# io8.net
KiCad netlist of a schematic drawn in EAGLE
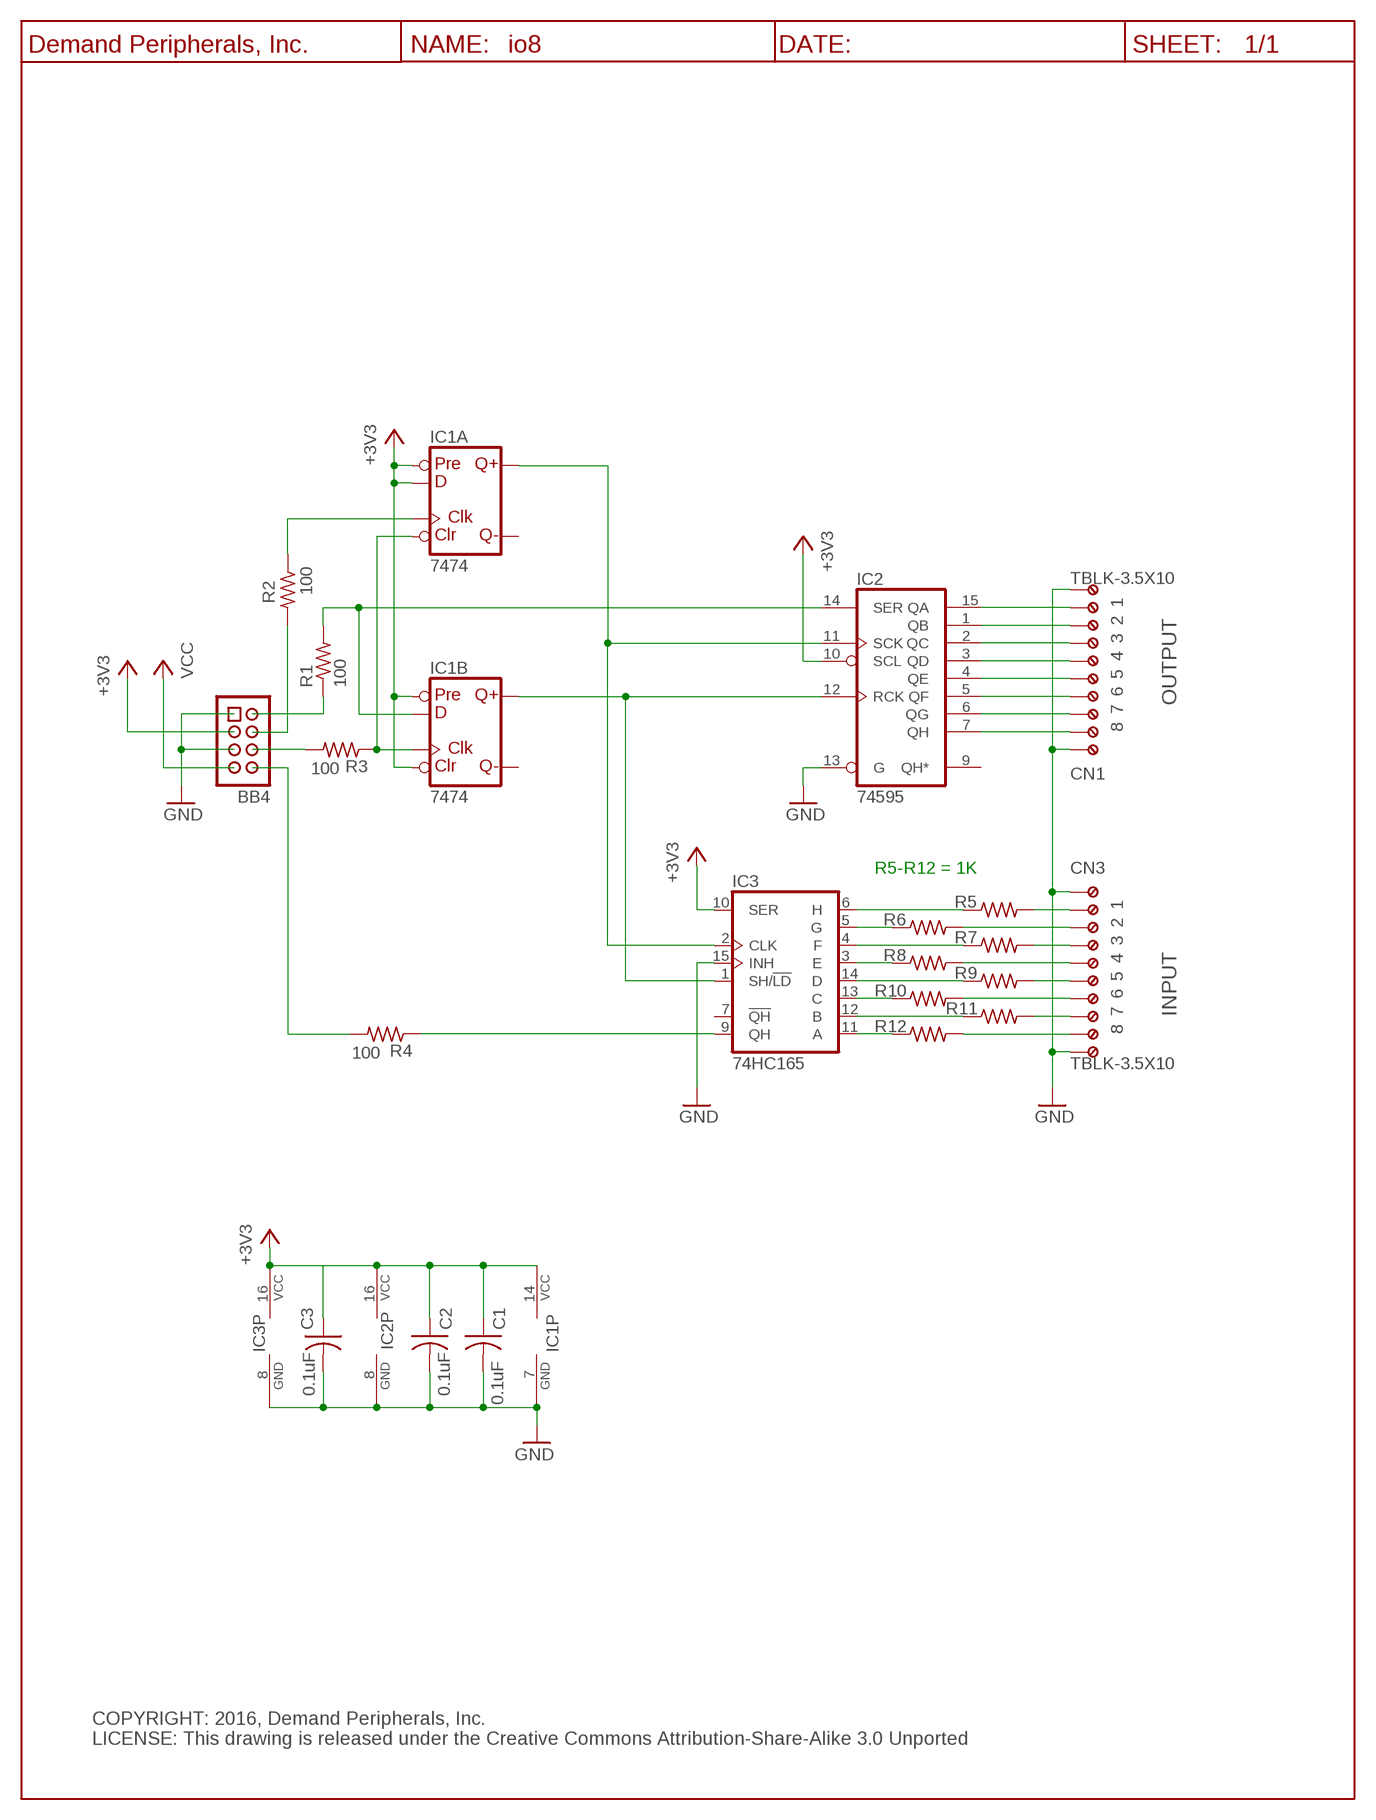
[diagram p0: schematic, sheet 1]

(export (version "E")
  (design (tool "Eeschema 10.0.6"))
  (components
    (comp (ref "BB4")
      (value "Hdr_4x2")
      (footprint "eagle-import:HDR-4X2")
      (libsource (lib "eagle-import") (part "HDR-4X2-SHR"))
    )
    (comp (ref "C1")
      (value "0.1uF")
      (footprint "eagle-import:C0603")
      (libsource (lib "eagle-import") (part "C0.1UF_C0603"))
    )
    (comp (ref "C2")
      (value "0.1uF")
      (footprint "eagle-import:C0603")
      (libsource (lib "eagle-import") (part "C0.1UF_C0603"))
    )
    (comp (ref "C3")
      (value "0.1uF")
      (footprint "eagle-import:C0603")
      (libsource (lib "eagle-import") (part "C0.1UF_C0603"))
    )
    (comp (ref "CN1")
      (value "TBLK-3.5X10")
      (footprint "eagle-import:TBLK-3.5X10")
      (libsource (lib "eagle-import") (part "TBLK-3.5X10"))
    )
    (comp (ref "CN3")
      (value "TBLK-3.5X10")
      (footprint "eagle-import:TBLK-3.5X10")
      (libsource (lib "eagle-import") (part "TBLK-3.5X10"))
    )
    (comp (ref "IC1")
      (value "7474")
      (footprint "eagle-import:SO14")
      (libsource (lib "eagle-import") (part "74AHC74"))
    )
    (comp (ref "IC2")
      (value "74595")
      (footprint "eagle-import:SO16")
      (libsource (lib "eagle-import") (part "74595"))
    )
    (comp (ref "IC3")
      (value "74HC165")
      (footprint "eagle-import:SO16")
      (libsource (lib "eagle-import") (part "74HC165"))
    )
    (comp (ref "R1")
      (value "100")
      (footprint "eagle-import:R0603")
      (libsource (lib "eagle-import") (part "R100_R0603"))
    )
    (comp (ref "R2")
      (value "100")
      (footprint "eagle-import:R0603")
      (libsource (lib "eagle-import") (part "R100_R0603"))
    )
    (comp (ref "R3")
      (value "100")
      (footprint "eagle-import:R0603")
      (libsource (lib "eagle-import") (part "R100_R0603"))
    )
    (comp (ref "R4")
      (value "100")
      (footprint "eagle-import:R0603")
      (libsource (lib "eagle-import") (part "R100_R0603"))
    )
    (comp (ref "R5")
      (value "R1K_R0603")
      (footprint "eagle-import:R0603")
      (libsource (lib "eagle-import") (part "R1K_R0603"))
    )
    (comp (ref "R6")
      (value "R1K_R0603")
      (footprint "eagle-import:R0603")
      (libsource (lib "eagle-import") (part "R1K_R0603"))
    )
    (comp (ref "R7")
      (value "R1K_R0603")
      (footprint "eagle-import:R0603")
      (libsource (lib "eagle-import") (part "R1K_R0603"))
    )
    (comp (ref "R8")
      (value "R1K_R0603")
      (footprint "eagle-import:R0603")
      (libsource (lib "eagle-import") (part "R1K_R0603"))
    )
    (comp (ref "R9")
      (value "R1K_R0603")
      (footprint "eagle-import:R0603")
      (libsource (lib "eagle-import") (part "R1K_R0603"))
    )
    (comp (ref "R10")
      (value "R1K_R0603")
      (footprint "eagle-import:R0603")
      (libsource (lib "eagle-import") (part "R1K_R0603"))
    )
    (comp (ref "R11")
      (value "R1K_R0603")
      (footprint "eagle-import:R0603")
      (libsource (lib "eagle-import") (part "R1K_R0603"))
    )
    (comp (ref "R12")
      (value "R1K_R0603")
      (footprint "eagle-import:R0603")
      (libsource (lib "eagle-import") (part "R1K_R0603"))
    )
    (comp (ref "U$5")
      (value "DP_FRAME_P")
      (footprint "eagle-import:P_FRAME")
      (libsource (lib "eagle-import") (part "DP_FRAME_P"))
    )
  )
  (nets
    (net (code "1") (name "+3V3") (class "Default")
      (node (ref "BB4") (pin "3") (pinfunction "3_3") (pintype "passive"))
      (node (ref "C1") (pin "1") (pinfunction "1_1") (pintype "passive"))
      (node (ref "C2") (pin "1") (pinfunction "1_1") (pintype "passive"))
      (node (ref "C3") (pin "1") (pinfunction "1_1") (pintype "passive"))
      (node (ref "IC1") (pin "10") (pinfunction "PRE_10") (pintype "input"))
      (node (ref "IC1") (pin "13") (pinfunction "CLR_13") (pintype "input"))
      (node (ref "IC1") (pin "14") (pinfunction "VCC_14") (pintype "power_in"))
      (node (ref "IC1") (pin "2") (pinfunction "D_2") (pintype "input"))
      (node (ref "IC1") (pin "4") (pinfunction "PRE_4") (pintype "input"))
      (node (ref "IC2") (pin "10") (pinfunction "SCL_10") (pintype "input"))
      (node (ref "IC2") (pin "16") (pinfunction "VCC_16") (pintype "power_in"))
      (node (ref "IC3") (pin "10") (pinfunction "SER_10") (pintype "input"))
      (node (ref "IC3") (pin "16") (pinfunction "VCC_16") (pintype "power_in"))
    )
    (net (code "2") (name "GND") (class "Default")
      (node (ref "BB4") (pin "1") (pinfunction "1_1") (pintype "passive"))
      (node (ref "BB4") (pin "5") (pinfunction "5_5") (pintype "passive"))
      (node (ref "C1") (pin "2") (pinfunction "2_2") (pintype "passive"))
      (node (ref "C2") (pin "2") (pinfunction "2_2") (pintype "passive"))
      (node (ref "C3") (pin "2") (pinfunction "2_2") (pintype "passive"))
      (node (ref "CN1") (pin "1") (pinfunction "KL_1") (pintype "passive"))
      (node (ref "CN1") (pin "10") (pinfunction "KL9_10") (pintype "passive"))
      (node (ref "CN3") (pin "1") (pinfunction "KL_1") (pintype "passive"))
      (node (ref "CN3") (pin "10") (pinfunction "KL9_10") (pintype "passive"))
      (node (ref "IC1") (pin "7") (pinfunction "GND_7") (pintype "power_in"))
      (node (ref "IC2") (pin "13") (pinfunction "G_13") (pintype "input"))
      (node (ref "IC2") (pin "8") (pinfunction "GND_8") (pintype "power_in"))
      (node (ref "IC3") (pin "15") (pinfunction "INH_15") (pintype "input"))
      (node (ref "IC3") (pin "8") (pinfunction "GND_8") (pintype "power_in"))
    )
    (net (code "3") (name "Net-(BB4-Pad2)") (class "Default")
      (node (ref "BB4") (pin "2") (pinfunction "2_2") (pintype "passive"))
      (node (ref "R1") (pin "1") (pinfunction "1_1") (pintype "passive"))
    )
    (net (code "4") (name "Net-(BB4-Pad4)") (class "Default")
      (node (ref "BB4") (pin "4") (pinfunction "4_4") (pintype "passive"))
      (node (ref "R2") (pin "2") (pinfunction "2_2") (pintype "passive"))
    )
    (net (code "5") (name "Net-(BB4-Pad6)") (class "Default")
      (node (ref "BB4") (pin "6") (pinfunction "6_6") (pintype "passive"))
      (node (ref "R3") (pin "2") (pinfunction "2_2") (pintype "passive"))
    )
    (net (code "6") (name "Net-(BB4-Pad8)") (class "Default")
      (node (ref "BB4") (pin "8") (pinfunction "8_8") (pintype "passive"))
      (node (ref "R4") (pin "2") (pinfunction "2_2") (pintype "passive"))
    )
    (net (code "7") (name "Net-(CN1-KL1)") (class "Default")
      (node (ref "CN1") (pin "2") (pinfunction "KL1_2") (pintype "passive"))
      (node (ref "IC2") (pin "7") (pinfunction "QH_7") (pintype "tri_state"))
    )
    (net (code "8") (name "Net-(CN1-KL2)") (class "Default")
      (node (ref "CN1") (pin "3") (pinfunction "KL2_3") (pintype "passive"))
      (node (ref "IC2") (pin "6") (pinfunction "QG_6") (pintype "tri_state"))
    )
    (net (code "9") (name "Net-(CN1-KL3)") (class "Default")
      (node (ref "CN1") (pin "4") (pinfunction "KL3_4") (pintype "passive"))
      (node (ref "IC2") (pin "5") (pinfunction "QF_5") (pintype "tri_state"))
    )
    (net (code "10") (name "Net-(CN1-KL4)") (class "Default")
      (node (ref "CN1") (pin "5") (pinfunction "KL4_5") (pintype "passive"))
      (node (ref "IC2") (pin "4") (pinfunction "QE_4") (pintype "tri_state"))
    )
    (net (code "11") (name "Net-(CN1-KL5)") (class "Default")
      (node (ref "CN1") (pin "6") (pinfunction "KL5_6") (pintype "passive"))
      (node (ref "IC2") (pin "3") (pinfunction "QD_3") (pintype "tri_state"))
    )
    (net (code "12") (name "Net-(CN1-KL6)") (class "Default")
      (node (ref "CN1") (pin "7") (pinfunction "KL6_7") (pintype "passive"))
      (node (ref "IC2") (pin "2") (pinfunction "QC_2") (pintype "tri_state"))
    )
    (net (code "13") (name "Net-(CN1-KL7)") (class "Default")
      (node (ref "CN1") (pin "8") (pinfunction "KL7_8") (pintype "passive"))
      (node (ref "IC2") (pin "1") (pinfunction "QB_1") (pintype "tri_state"))
    )
    (net (code "14") (name "Net-(CN1-KL8)") (class "Default")
      (node (ref "CN1") (pin "9") (pinfunction "KL8_9") (pintype "passive"))
      (node (ref "IC2") (pin "15") (pinfunction "QA_15") (pintype "tri_state"))
    )
    (net (code "15") (name "Net-(CN3-KL1)") (class "Default")
      (node (ref "CN3") (pin "2") (pinfunction "KL1_2") (pintype "passive"))
      (node (ref "R5") (pin "2") (pinfunction "2_2") (pintype "passive"))
    )
    (net (code "16") (name "Net-(CN3-KL2)") (class "Default")
      (node (ref "CN3") (pin "3") (pinfunction "KL2_3") (pintype "passive"))
      (node (ref "R6") (pin "2") (pinfunction "2_2") (pintype "passive"))
    )
    (net (code "17") (name "Net-(CN3-KL3)") (class "Default")
      (node (ref "CN3") (pin "4") (pinfunction "KL3_4") (pintype "passive"))
      (node (ref "R7") (pin "2") (pinfunction "2_2") (pintype "passive"))
    )
    (net (code "18") (name "Net-(CN3-KL4)") (class "Default")
      (node (ref "CN3") (pin "5") (pinfunction "KL4_5") (pintype "passive"))
      (node (ref "R8") (pin "2") (pinfunction "2_2") (pintype "passive"))
    )
    (net (code "19") (name "Net-(CN3-KL5)") (class "Default")
      (node (ref "CN3") (pin "6") (pinfunction "KL5_6") (pintype "passive"))
      (node (ref "R9") (pin "2") (pinfunction "2_2") (pintype "passive"))
    )
    (net (code "20") (name "Net-(CN3-KL6)") (class "Default")
      (node (ref "CN3") (pin "7") (pinfunction "KL6_7") (pintype "passive"))
      (node (ref "R10") (pin "2") (pinfunction "2_2") (pintype "passive"))
    )
    (net (code "21") (name "Net-(CN3-KL7)") (class "Default")
      (node (ref "CN3") (pin "8") (pinfunction "KL7_8") (pintype "passive"))
      (node (ref "R11") (pin "2") (pinfunction "2_2") (pintype "passive"))
    )
    (net (code "22") (name "Net-(CN3-KL8)") (class "Default")
      (node (ref "CN3") (pin "9") (pinfunction "KL8_9") (pintype "passive"))
      (node (ref "R12") (pin "2") (pinfunction "2_2") (pintype "passive"))
    )
    (net (code "23") (name "Net-(IC1A-CLK)") (class "Default")
      (node (ref "IC1") (pin "3") (pinfunction "CLK_3") (pintype "input"))
      (node (ref "R2") (pin "1") (pinfunction "1_1") (pintype "passive"))
    )
    (net (code "24") (name "Net-(IC1A-CLR)") (class "Default")
      (node (ref "IC1") (pin "1") (pinfunction "CLR_1") (pintype "input"))
      (node (ref "IC1") (pin "11") (pinfunction "CLK_11") (pintype "input"))
      (node (ref "R3") (pin "1") (pinfunction "1_1") (pintype "passive"))
    )
    (net (code "25") (name "Net-(IC1A-Q)") (class "Default")
      (node (ref "IC1") (pin "5") (pinfunction "Q_5") (pintype "output"))
      (node (ref "IC2") (pin "11") (pinfunction "SCK_11") (pintype "input"))
      (node (ref "IC3") (pin "2") (pinfunction "CLK_2") (pintype "input"))
    )
    (net (code "26") (name "Net-(IC1B-D)") (class "Default")
      (node (ref "IC1") (pin "12") (pinfunction "D_12") (pintype "input"))
      (node (ref "IC2") (pin "14") (pinfunction "SER_14") (pintype "input"))
      (node (ref "R1") (pin "2") (pinfunction "2_2") (pintype "passive"))
    )
    (net (code "27") (name "Net-(IC1B-Q)") (class "Default")
      (node (ref "IC1") (pin "9") (pinfunction "Q_9") (pintype "output"))
      (node (ref "IC2") (pin "12") (pinfunction "RCK_12") (pintype "input"))
      (node (ref "IC3") (pin "1") (pinfunction "SH/~{LD}_1") (pintype "input"))
    )
    (net (code "28") (name "Net-(IC3A-A)") (class "Default")
      (node (ref "IC3") (pin "11") (pinfunction "A_11") (pintype "input"))
      (node (ref "R12") (pin "1") (pinfunction "1_1") (pintype "passive"))
    )
    (net (code "29") (name "Net-(IC3A-B)") (class "Default")
      (node (ref "IC3") (pin "12") (pinfunction "B_12") (pintype "input"))
      (node (ref "R11") (pin "1") (pinfunction "1_1") (pintype "passive"))
    )
    (net (code "30") (name "Net-(IC3A-C)") (class "Default")
      (node (ref "IC3") (pin "13") (pinfunction "C_13") (pintype "input"))
      (node (ref "R10") (pin "1") (pinfunction "1_1") (pintype "passive"))
    )
    (net (code "31") (name "Net-(IC3A-D)") (class "Default")
      (node (ref "IC3") (pin "14") (pinfunction "D_14") (pintype "input"))
      (node (ref "R9") (pin "1") (pinfunction "1_1") (pintype "passive"))
    )
    (net (code "32") (name "Net-(IC3A-E)") (class "Default")
      (node (ref "IC3") (pin "3") (pinfunction "E_3") (pintype "input"))
      (node (ref "R8") (pin "1") (pinfunction "1_1") (pintype "passive"))
    )
    (net (code "33") (name "Net-(IC3A-F)") (class "Default")
      (node (ref "IC3") (pin "4") (pinfunction "F_4") (pintype "input"))
      (node (ref "R7") (pin "1") (pinfunction "1_1") (pintype "passive"))
    )
    (net (code "34") (name "Net-(IC3A-G)") (class "Default")
      (node (ref "IC3") (pin "5") (pinfunction "G_5") (pintype "input"))
      (node (ref "R6") (pin "1") (pinfunction "1_1") (pintype "passive"))
    )
    (net (code "35") (name "Net-(IC3A-H)") (class "Default")
      (node (ref "IC3") (pin "6") (pinfunction "H_6") (pintype "input"))
      (node (ref "R5") (pin "1") (pinfunction "1_1") (pintype "passive"))
    )
    (net (code "36") (name "Net-(IC3A-QH)") (class "Default")
      (node (ref "IC3") (pin "9") (pinfunction "QH_9") (pintype "output"))
      (node (ref "R4") (pin "1") (pinfunction "1_1") (pintype "passive"))
    )
    (net (code "37") (name "VCC") (class "Default")
      (node (ref "BB4") (pin "7") (pinfunction "7_7") (pintype "passive"))
    )
    (net (code "38") (name "unconnected-(IC1A-~{Q}-Pad6)") (class "Default")
      (node (ref "IC1") (pin "6") (pinfunction "~{Q}_6") (pintype "output"))
    )
    (net (code "39") (name "unconnected-(IC1B-~{Q}-Pad8)") (class "Default")
      (node (ref "IC1") (pin "8") (pinfunction "~{Q}_8") (pintype "output"))
    )
    (net (code "40") (name "unconnected-(IC2A-QH*-Pad9)") (class "Default")
      (node (ref "IC2") (pin "9") (pinfunction "QH*_9") (pintype "tri_state"))
    )
    (net (code "41") (name "unconnected-(IC3A-~{QH}-Pad7)") (class "Default")
      (node (ref "IC3") (pin "7") (pinfunction "~{QH}_7") (pintype "output"))
    )
  )
)
